# ASD2613.net
KiCad netlist of a schematic drawn in EAGLE
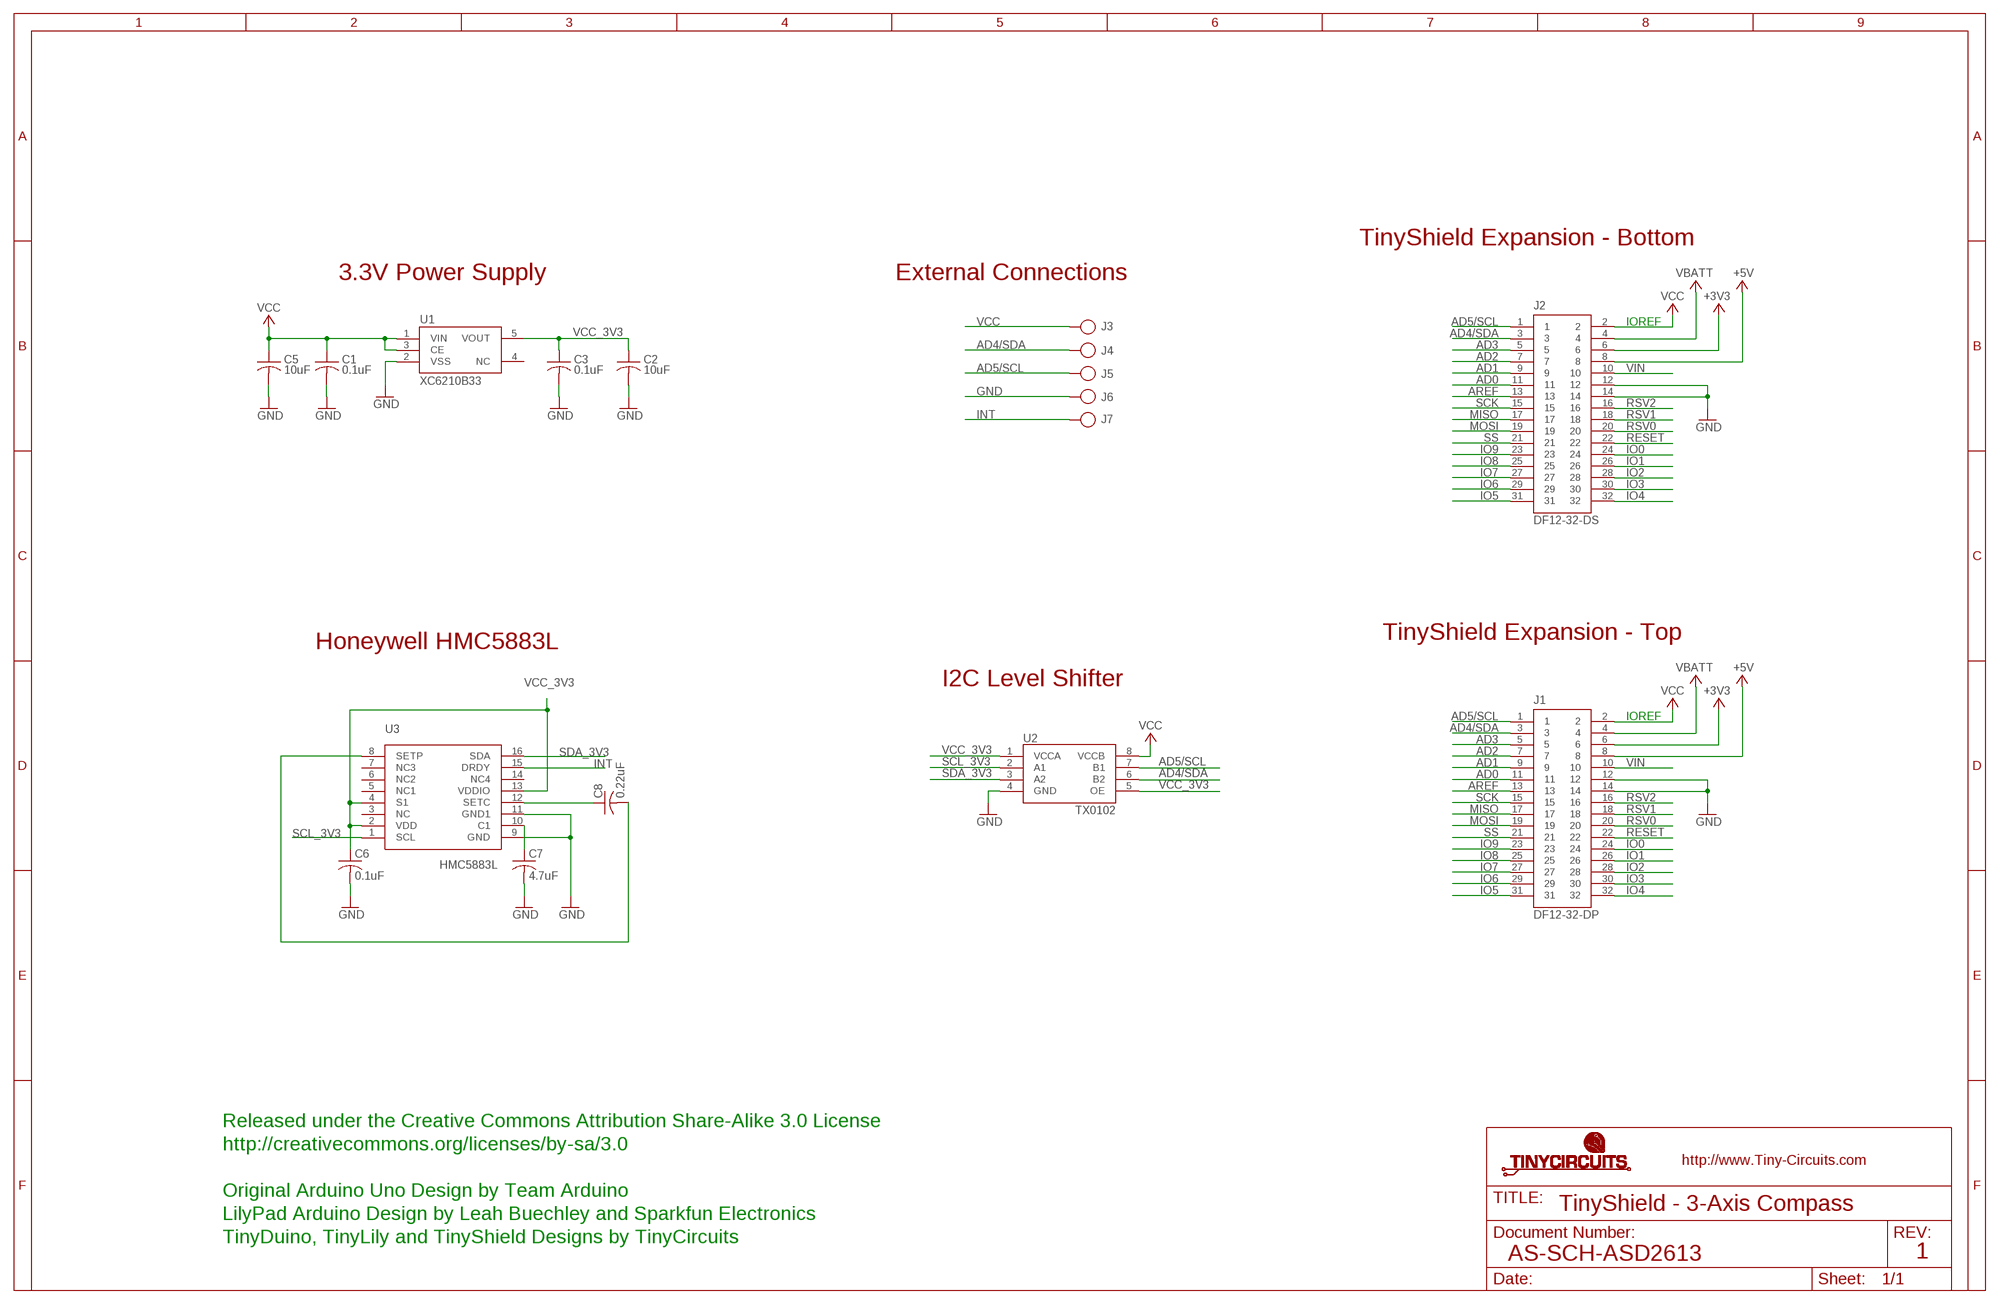
[diagram p0: schematic, sheet 1]

(export (version "E")
  (design (tool "Eeschema 10.0.6"))
  (components
    (comp (ref "C1")
      (value "0.1uF")
      (footprint "eagle-import:C0402")
      (fields (field (name "PARTNO") "AS-ITM-00008") (field (name "PARTNO_1") "AS-ITM-00008"))
      (libsource (lib "eagle-import") (part "AS-ITM-00008"))
    )
    (comp (ref "C2")
      (value "10uF")
      (footprint "eagle-import:C0805")
      (fields (field (name "PARTNO") "AS-ITM-00045") (field (name "PARTNO_1") "AS-ITM-00045"))
      (libsource (lib "eagle-import") (part "AS-ITM-00045"))
    )
    (comp (ref "C3")
      (value "0.1uF")
      (footprint "eagle-import:C0402")
      (fields (field (name "PARTNO") "AS-ITM-00008") (field (name "PARTNO_1") "AS-ITM-00008"))
      (libsource (lib "eagle-import") (part "AS-ITM-00008"))
    )
    (comp (ref "C5")
      (value "10uF")
      (footprint "eagle-import:C0805")
      (fields (field (name "PARTNO") "AS-ITM-00045"))
      (libsource (lib "eagle-import") (part "AS-ITM-00045"))
    )
    (comp (ref "C6")
      (value "0.1uF")
      (footprint "eagle-import:C0402")
      (fields (field (name "PARTNO") "AS-ITM-00008"))
      (libsource (lib "eagle-import") (part "AS-ITM-00008"))
    )
    (comp (ref "C7")
      (value "4.7uF")
      (footprint "eagle-import:C0603")
      (libsource (lib "eagle-import") (part "AS-ITM-00088"))
    )
    (comp (ref "C8")
      (value "0.22uF")
      (footprint "eagle-import:0402")
      (libsource (lib "eagle-import") (part "AS-ITM-00087"))
    )
    (comp (ref "J1")
      (value "DF12-32-DP")
      (footprint "eagle-import:DF12-32-DP")
      (fields (field (name "PARTNO") "AS-ITM-00015") (field (name "PARTNO_1") "AS-ITM-00015"))
      (libsource (lib "eagle-import") (part "AS-ITM-00015"))
    )
    (comp (ref "J2")
      (value "DF12-32-DS")
      (footprint "eagle-import:DF12-32-DS")
      (fields (field (name "PARTNO") "AS-ITM-00012") (field (name "PARTNO_1") "AS-ITM-00012"))
      (libsource (lib "eagle-import") (part "AS-ITM-00012"))
    )
    (comp (ref "J3")
      (value "PIN_1X.1\"")
      (footprint "eagle-import:1X.1_")
      (libsource (lib "eagle-import") (part "PIN_1X.1{dblquote}"))
    )
    (comp (ref "J4")
      (value "PIN_1X.1\"")
      (footprint "eagle-import:1X.1_")
      (libsource (lib "eagle-import") (part "PIN_1X.1{dblquote}"))
    )
    (comp (ref "J5")
      (value "PIN_1X.1\"")
      (footprint "eagle-import:1X.1_")
      (libsource (lib "eagle-import") (part "PIN_1X.1{dblquote}"))
    )
    (comp (ref "J6")
      (value "PIN_1X.1\"")
      (footprint "eagle-import:1X.1_")
      (libsource (lib "eagle-import") (part "PIN_1X.1{dblquote}"))
    )
    (comp (ref "J7")
      (value "PIN_1X.1\"")
      (footprint "eagle-import:1X.1_")
      (libsource (lib "eagle-import") (part "PIN_1X.1{dblquote}"))
    )
    (comp (ref "U1")
      (value "XC6210B33")
      (footprint "eagle-import:SOT-25")
      (fields (field (name "PARTNO") "AS-ITM-00046"))
      (libsource (lib "eagle-import") (part "AS-ITM-00046"))
    )
    (comp (ref "U2")
      (value "TX0102")
      (footprint "eagle-import:DQE(R-PX2SON-N8)")
      (fields (field (name "PARTNO") "AS-ITM-00073"))
      (libsource (lib "eagle-import") (part "AS-ITM-00073"))
    )
    (comp (ref "U3")
      (value "HMC5883L")
      (footprint "eagle-import:HMC5883L")
      (libsource (lib "eagle-import") (part "AS-ITM-00086"))
    )
  )
  (nets
    (net (code "1") (name "+3V3") (class "Default")
      (node (ref "J1") (pin "6") (pinfunction "6_6") (pintype "bidirectional"))
      (node (ref "J2") (pin "6") (pinfunction "6_6") (pintype "bidirectional"))
    )
    (net (code "2") (name "+5V") (class "Default")
      (node (ref "J1") (pin "8") (pinfunction "8_8") (pintype "bidirectional"))
      (node (ref "J2") (pin "8") (pinfunction "8_8") (pintype "bidirectional"))
    )
    (net (code "3") (name "/AD0") (class "Default")
      (node (ref "J1") (pin "11") (pinfunction "11_11") (pintype "bidirectional"))
      (node (ref "J2") (pin "11") (pinfunction "11_11") (pintype "bidirectional"))
    )
    (net (code "4") (name "/AD1") (class "Default")
      (node (ref "J1") (pin "9") (pinfunction "9_9") (pintype "bidirectional"))
      (node (ref "J2") (pin "9") (pinfunction "9_9") (pintype "bidirectional"))
    )
    (net (code "5") (name "/AD2") (class "Default")
      (node (ref "J1") (pin "7") (pinfunction "7_7") (pintype "bidirectional"))
      (node (ref "J2") (pin "7") (pinfunction "7_7") (pintype "bidirectional"))
    )
    (net (code "6") (name "/AD3") (class "Default")
      (node (ref "J1") (pin "5") (pinfunction "5_5") (pintype "bidirectional"))
      (node (ref "J2") (pin "5") (pinfunction "5_5") (pintype "bidirectional"))
    )
    (net (code "7") (name "/AD4{slash}SDA") (class "Default")
      (node (ref "J1") (pin "3") (pinfunction "3_3") (pintype "bidirectional"))
      (node (ref "J2") (pin "3") (pinfunction "3_3") (pintype "bidirectional"))
      (node (ref "J4") (pin "1") (pinfunction "1_1") (pintype "bidirectional"))
      (node (ref "U2") (pin "6") (pinfunction "B2_6") (pintype "bidirectional"))
    )
    (net (code "8") (name "/AD5{slash}SCL") (class "Default")
      (node (ref "J1") (pin "1") (pinfunction "1_1") (pintype "bidirectional"))
      (node (ref "J2") (pin "1") (pinfunction "1_1") (pintype "bidirectional"))
      (node (ref "J5") (pin "1") (pinfunction "1_1") (pintype "bidirectional"))
      (node (ref "U2") (pin "7") (pinfunction "B1_7") (pintype "bidirectional"))
    )
    (net (code "9") (name "/AREF") (class "Default")
      (node (ref "J1") (pin "13") (pinfunction "13_13") (pintype "bidirectional"))
      (node (ref "J2") (pin "13") (pinfunction "13_13") (pintype "bidirectional"))
    )
    (net (code "10") (name "/INT") (class "Default")
      (node (ref "J7") (pin "1") (pinfunction "1_1") (pintype "bidirectional"))
      (node (ref "U3") (pin "15") (pinfunction "DRDY_15") (pintype "bidirectional"))
    )
    (net (code "11") (name "/IO0") (class "Default")
      (node (ref "J1") (pin "24") (pinfunction "24_24") (pintype "bidirectional"))
      (node (ref "J2") (pin "24") (pinfunction "24_24") (pintype "bidirectional"))
    )
    (net (code "12") (name "/IO1") (class "Default")
      (node (ref "J1") (pin "26") (pinfunction "26_26") (pintype "bidirectional"))
      (node (ref "J2") (pin "26") (pinfunction "26_26") (pintype "bidirectional"))
    )
    (net (code "13") (name "/IO2") (class "Default")
      (node (ref "J1") (pin "28") (pinfunction "28_28") (pintype "bidirectional"))
      (node (ref "J2") (pin "28") (pinfunction "28_28") (pintype "bidirectional"))
    )
    (net (code "14") (name "/IO3") (class "Default")
      (node (ref "J1") (pin "30") (pinfunction "30_30") (pintype "bidirectional"))
      (node (ref "J2") (pin "30") (pinfunction "30_30") (pintype "bidirectional"))
    )
    (net (code "15") (name "/IO4") (class "Default")
      (node (ref "J1") (pin "32") (pinfunction "32_32") (pintype "bidirectional"))
      (node (ref "J2") (pin "32") (pinfunction "32_32") (pintype "bidirectional"))
    )
    (net (code "16") (name "/IO5") (class "Default")
      (node (ref "J1") (pin "31") (pinfunction "31_31") (pintype "bidirectional"))
      (node (ref "J2") (pin "31") (pinfunction "31_31") (pintype "bidirectional"))
    )
    (net (code "17") (name "/IO6") (class "Default")
      (node (ref "J1") (pin "29") (pinfunction "29_29") (pintype "bidirectional"))
      (node (ref "J2") (pin "29") (pinfunction "29_29") (pintype "bidirectional"))
    )
    (net (code "18") (name "/IO7") (class "Default")
      (node (ref "J1") (pin "27") (pinfunction "27_27") (pintype "bidirectional"))
      (node (ref "J2") (pin "27") (pinfunction "27_27") (pintype "bidirectional"))
    )
    (net (code "19") (name "/IO8") (class "Default")
      (node (ref "J1") (pin "25") (pinfunction "25_25") (pintype "bidirectional"))
      (node (ref "J2") (pin "25") (pinfunction "25_25") (pintype "bidirectional"))
    )
    (net (code "20") (name "/IO9") (class "Default")
      (node (ref "J1") (pin "23") (pinfunction "23_23") (pintype "bidirectional"))
      (node (ref "J2") (pin "23") (pinfunction "23_23") (pintype "bidirectional"))
    )
    (net (code "21") (name "/MISO") (class "Default")
      (node (ref "J1") (pin "17") (pinfunction "17_17") (pintype "bidirectional"))
      (node (ref "J2") (pin "17") (pinfunction "17_17") (pintype "bidirectional"))
    )
    (net (code "22") (name "/MOSI") (class "Default")
      (node (ref "J1") (pin "19") (pinfunction "19_19") (pintype "bidirectional"))
      (node (ref "J2") (pin "19") (pinfunction "19_19") (pintype "bidirectional"))
    )
    (net (code "23") (name "/RESET") (class "Default")
      (node (ref "J1") (pin "22") (pinfunction "22_22") (pintype "bidirectional"))
      (node (ref "J2") (pin "22") (pinfunction "22_22") (pintype "bidirectional"))
    )
    (net (code "24") (name "/RSV0") (class "Default")
      (node (ref "J1") (pin "20") (pinfunction "20_20") (pintype "bidirectional"))
      (node (ref "J2") (pin "20") (pinfunction "20_20") (pintype "bidirectional"))
    )
    (net (code "25") (name "/RSV1") (class "Default")
      (node (ref "J1") (pin "18") (pinfunction "18_18") (pintype "bidirectional"))
      (node (ref "J2") (pin "18") (pinfunction "18_18") (pintype "bidirectional"))
    )
    (net (code "26") (name "/RSV2") (class "Default")
      (node (ref "J1") (pin "16") (pinfunction "16_16") (pintype "bidirectional"))
      (node (ref "J2") (pin "16") (pinfunction "16_16") (pintype "bidirectional"))
    )
    (net (code "27") (name "/SCK") (class "Default")
      (node (ref "J1") (pin "15") (pinfunction "15_15") (pintype "bidirectional"))
      (node (ref "J2") (pin "15") (pinfunction "15_15") (pintype "bidirectional"))
    )
    (net (code "28") (name "/SCL_3V3") (class "Default")
      (node (ref "U2") (pin "2") (pinfunction "A1_2") (pintype "bidirectional"))
      (node (ref "U3") (pin "1") (pinfunction "SCL_1") (pintype "bidirectional"))
    )
    (net (code "29") (name "/SDA_3V3") (class "Default")
      (node (ref "U2") (pin "3") (pinfunction "A2_3") (pintype "bidirectional"))
      (node (ref "U3") (pin "16") (pinfunction "SDA_16") (pintype "bidirectional"))
    )
    (net (code "30") (name "/SS") (class "Default")
      (node (ref "J1") (pin "21") (pinfunction "21_21") (pintype "bidirectional"))
      (node (ref "J2") (pin "21") (pinfunction "21_21") (pintype "bidirectional"))
    )
    (net (code "31") (name "/VCC_3V3") (class "Default")
      (node (ref "C2") (pin "1") (pinfunction "1_1") (pintype "passive"))
      (node (ref "C3") (pin "1") (pinfunction "1_1") (pintype "passive"))
      (node (ref "C6") (pin "1") (pinfunction "1_1") (pintype "passive"))
      (node (ref "U1") (pin "5") (pinfunction "VOUT_5") (pintype "bidirectional"))
      (node (ref "U2") (pin "1") (pinfunction "VCCA_1") (pintype "bidirectional"))
      (node (ref "U2") (pin "5") (pinfunction "OE_5") (pintype "bidirectional"))
      (node (ref "U3") (pin "13") (pinfunction "VDDIO_13") (pintype "bidirectional"))
      (node (ref "U3") (pin "2") (pinfunction "VDD_2") (pintype "bidirectional"))
      (node (ref "U3") (pin "4") (pinfunction "S1_4") (pintype "bidirectional"))
    )
    (net (code "32") (name "/VIN") (class "Default")
      (node (ref "J1") (pin "10") (pinfunction "10_10") (pintype "bidirectional"))
      (node (ref "J2") (pin "10") (pinfunction "10_10") (pintype "bidirectional"))
    )
    (net (code "33") (name "GND") (class "Default")
      (node (ref "C1") (pin "2") (pinfunction "2_2") (pintype "passive"))
      (node (ref "C2") (pin "2") (pinfunction "2_2") (pintype "passive"))
      (node (ref "C3") (pin "2") (pinfunction "2_2") (pintype "passive"))
      (node (ref "C5") (pin "2") (pinfunction "2_2") (pintype "passive"))
      (node (ref "C6") (pin "2") (pinfunction "2_2") (pintype "passive"))
      (node (ref "C7") (pin "2") (pinfunction "2_2") (pintype "passive"))
      (node (ref "J1") (pin "12") (pinfunction "12_12") (pintype "bidirectional"))
      (node (ref "J1") (pin "14") (pinfunction "14_14") (pintype "bidirectional"))
      (node (ref "J2") (pin "12") (pinfunction "12_12") (pintype "bidirectional"))
      (node (ref "J2") (pin "14") (pinfunction "14_14") (pintype "bidirectional"))
      (node (ref "J6") (pin "1") (pinfunction "1_1") (pintype "bidirectional"))
      (node (ref "U1") (pin "2") (pinfunction "VSS_2") (pintype "power_in"))
      (node (ref "U2") (pin "4") (pinfunction "GND_4") (pintype "bidirectional"))
      (node (ref "U3") (pin "11") (pinfunction "GND1_11") (pintype "bidirectional"))
      (node (ref "U3") (pin "9") (pinfunction "GND_9") (pintype "bidirectional"))
    )
    (net (code "34") (name "Net-(U3-C1)") (class "Default")
      (node (ref "C7") (pin "1") (pinfunction "1_1") (pintype "passive"))
      (node (ref "U3") (pin "10") (pinfunction "C1_10") (pintype "bidirectional"))
    )
    (net (code "35") (name "Net-(U3-SETC)") (class "Default")
      (node (ref "C8") (pin "1") (pinfunction "1_1") (pintype "passive"))
      (node (ref "U3") (pin "12") (pinfunction "SETC_12") (pintype "bidirectional"))
    )
    (net (code "36") (name "Net-(U3-SETP)") (class "Default")
      (node (ref "C8") (pin "2") (pinfunction "2_2") (pintype "passive"))
      (node (ref "U3") (pin "8") (pinfunction "SETP_8") (pintype "bidirectional"))
    )
    (net (code "37") (name "VBATT") (class "Default")
      (node (ref "J1") (pin "4") (pinfunction "4_4") (pintype "bidirectional"))
      (node (ref "J2") (pin "4") (pinfunction "4_4") (pintype "bidirectional"))
    )
    (net (code "38") (name "VCC") (class "Default")
      (node (ref "C1") (pin "1") (pinfunction "1_1") (pintype "passive"))
      (node (ref "C5") (pin "1") (pinfunction "1_1") (pintype "passive"))
      (node (ref "J1") (pin "2") (pinfunction "2_2") (pintype "bidirectional"))
      (node (ref "J2") (pin "2") (pinfunction "2_2") (pintype "bidirectional"))
      (node (ref "J3") (pin "1") (pinfunction "1_1") (pintype "bidirectional"))
      (node (ref "U1") (pin "1") (pinfunction "VIN_1") (pintype "bidirectional"))
      (node (ref "U1") (pin "3") (pinfunction "CE_3") (pintype "bidirectional"))
      (node (ref "U2") (pin "8") (pinfunction "VCCB_8") (pintype "bidirectional"))
    )
    (net (code "39") (name "unconnected-(U1-NC-Pad4)") (class "Default")
      (node (ref "U1") (pin "4") (pinfunction "NC_4") (pintype "bidirectional"))
    )
    (net (code "40") (name "unconnected-(U3-NC-Pad3)") (class "Default")
      (node (ref "U3") (pin "3") (pinfunction "NC_3") (pintype "bidirectional"))
    )
    (net (code "41") (name "unconnected-(U3-NC1-Pad5)") (class "Default")
      (node (ref "U3") (pin "5") (pinfunction "NC1_5") (pintype "bidirectional"))
    )
    (net (code "42") (name "unconnected-(U3-NC2-Pad6)") (class "Default")
      (node (ref "U3") (pin "6") (pinfunction "NC2_6") (pintype "bidirectional"))
    )
    (net (code "43") (name "unconnected-(U3-NC3-Pad7)") (class "Default")
      (node (ref "U3") (pin "7") (pinfunction "NC3_7") (pintype "bidirectional"))
    )
    (net (code "44") (name "unconnected-(U3-NC4-Pad14)") (class "Default")
      (node (ref "U3") (pin "14") (pinfunction "NC4_14") (pintype "bidirectional"))
    )
  )
)
